# rc2014-graphics-card.net
KiCad netlist of a schematic drawn in EAGLE
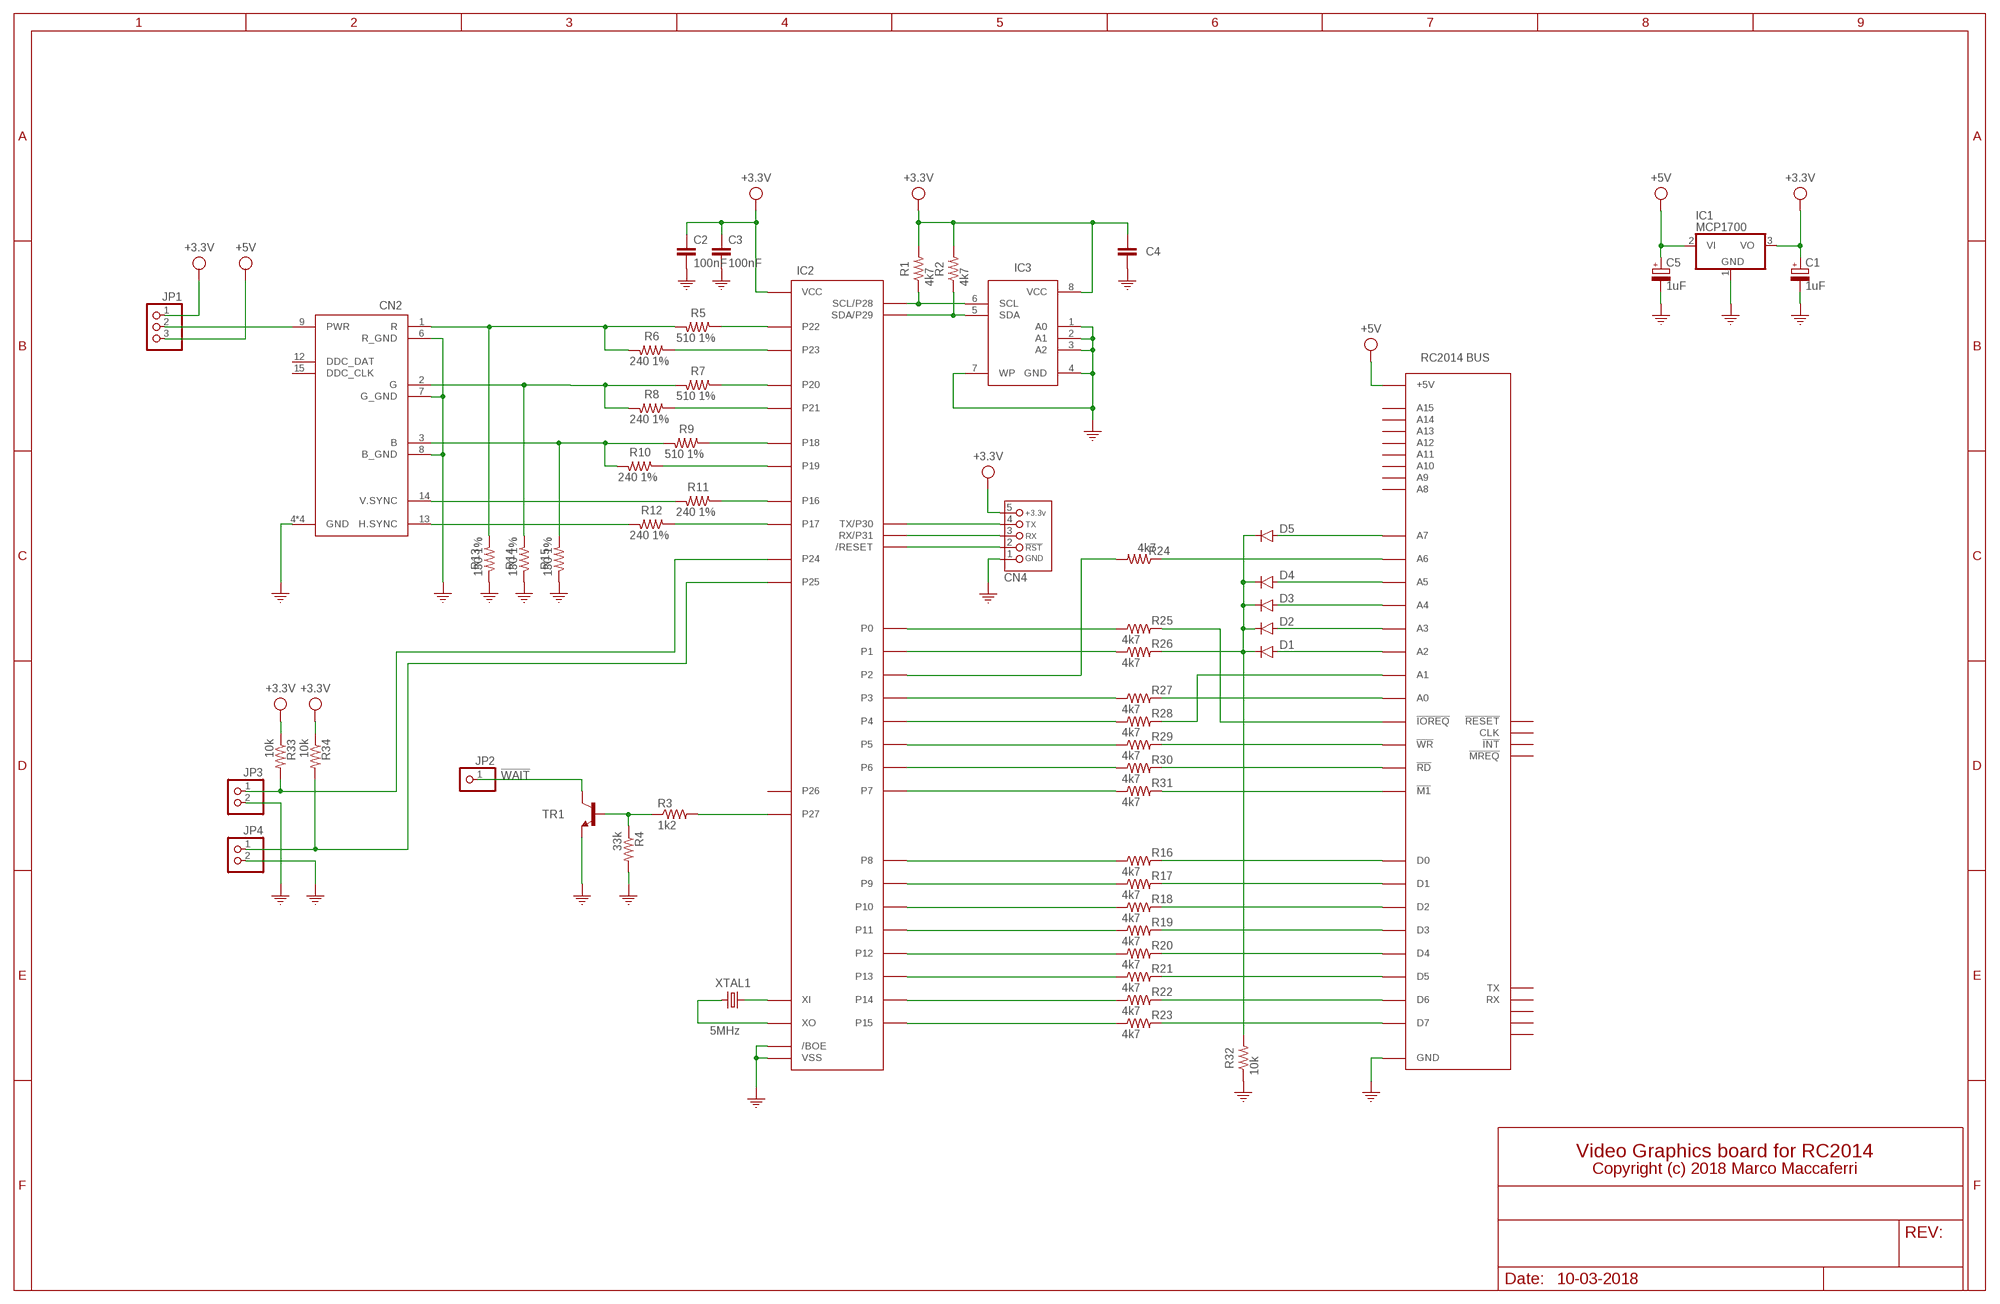
[diagram p0: schematic, sheet 1]

(export (version "E")
  (design (tool "Eeschema 10.0.6"))
  (components
    (comp (ref "C1")
      (value "1uF")
      (footprint "eagle-import:E2,5-6")
      (fields (field (name "MPN") "ESK105M050AC3AA"))
      (libsource (lib "eagle-import") (part "CP-2.5-6"))
    )
    (comp (ref "C2")
      (value "100nF")
      (footprint "eagle-import:C050-025X075")
      (fields (field (name "MPN") "R82EC3100AA70J"))
      (libsource (lib "eagle-import") (part "C"))
    )
    (comp (ref "C3")
      (value "100nF")
      (footprint "eagle-import:C050-025X075")
      (fields (field (name "MPN") "R82EC3100AA70J"))
      (libsource (lib "eagle-import") (part "C"))
    )
    (comp (ref "C4")
      (value "100nF")
      (footprint "eagle-import:C050-025X075")
      (fields (field (name "MPN") "R82EC3100AA70J"))
      (libsource (lib "eagle-import") (part "C"))
    )
    (comp (ref "C5")
      (value "1uF")
      (footprint "eagle-import:E2,5-6")
      (fields (field (name "MPN") "ESK105M050AC3AA"))
      (libsource (lib "eagle-import") (part "CP-2.5-6"))
    )
    (comp (ref "CN1")
      (value "RC2014BUS")
      (footprint "eagle-import:RC2014BUS")
      (fields (field (name "MPN") "PRPC040SBAN-M71RC"))
      (libsource (lib "eagle-import") (part "RC2014BUS"))
    )
    (comp (ref "CN2")
      (value "VGA")
      (footprint "eagle-import:VGA")
      (fields (field (name "MPN") "1734344-1"))
      (libsource (lib "eagle-import") (part "VGA"))
    )
    (comp (ref "CN4")
      (value "PROPELLER_ICSP_HEADER")
      (footprint "eagle-import:HEADER_PRG_1X05")
      (fields (field (name "MPN") "PRPC005SAAN-RC"))
      (libsource (lib "eagle-import") (part "PROPELLER_ICSP_HEADER"))
    )
    (comp (ref "D1")
      (value "1N4148DO35-7")
      (footprint "eagle-import:DO35-7")
      (libsource (lib "eagle-import") (part "1N4148DO35-7"))
    )
    (comp (ref "D2")
      (value "1N4148DO35-7")
      (footprint "eagle-import:DO35-7")
      (libsource (lib "eagle-import") (part "1N4148DO35-7"))
    )
    (comp (ref "D3")
      (value "1N4148DO35-7")
      (footprint "eagle-import:DO35-7")
      (libsource (lib "eagle-import") (part "1N4148DO35-7"))
    )
    (comp (ref "D4")
      (value "1N4148DO35-7")
      (footprint "eagle-import:DO35-7")
      (libsource (lib "eagle-import") (part "1N4148DO35-7"))
    )
    (comp (ref "D5")
      (value "1N4148DO35-7")
      (footprint "eagle-import:DO35-7")
      (libsource (lib "eagle-import") (part "1N4148DO35-7"))
    )
    (comp (ref "IC1")
      (value "MCP1700")
      (footprint "eagle-import:TO92")
      (fields (field (name "MPN") "MCP1700-3302E/TO"))
      (libsource (lib "eagle-import") (part "MCP1700"))
    )
    (comp (ref "IC2")
      (value "P8X32A-B-D40")
      (footprint "eagle-import:DIL40")
      (fields (field (name "MPN") "P8X32A-D40"))
      (libsource (lib "eagle-import") (part "P8X32A-B-D40"))
    )
    (comp (ref "IC3")
      (value "24LC512-I/P")
      (footprint "eagle-import:DIL08")
      (fields (field (name "MPN") "24LC256-I/P"))
      (libsource (lib "eagle-import") (part "24LC-I/P512"))
    )
    (comp (ref "JP1")
      (value "PINHD-1X3")
      (footprint "eagle-import:1X03")
      (libsource (lib "eagle-import") (part "PINHD-1X3"))
    )
    (comp (ref "JP2")
      (value "PINHD-1X1")
      (footprint "eagle-import:1X01")
      (libsource (lib "eagle-import") (part "PINHD-1X1"))
    )
    (comp (ref "JP3")
      (value "PINHD-1X2")
      (footprint "eagle-import:1X02")
      (libsource (lib "eagle-import") (part "PINHD-1X2"))
    )
    (comp (ref "JP4")
      (value "PINHD-1X2")
      (footprint "eagle-import:1X02")
      (libsource (lib "eagle-import") (part "PINHD-1X2"))
    )
    (comp (ref "R1")
      (value "4k7")
      (footprint "eagle-import:0207_10")
      (fields (field (name "MPN") "CFR-25JB-52-4K7"))
      (libsource (lib "eagle-import") (part "R-1/4W"))
    )
    (comp (ref "R2")
      (value "4k7")
      (footprint "eagle-import:0207_10")
      (fields (field (name "MPN") "CFR-25JB-52-4K7"))
      (libsource (lib "eagle-import") (part "R-1/4W"))
    )
    (comp (ref "R3")
      (value "1k2")
      (footprint "eagle-import:0207_10")
      (libsource (lib "eagle-import") (part "R-1/4W"))
    )
    (comp (ref "R4")
      (value "33k")
      (footprint "eagle-import:0204_7")
      (libsource (lib "eagle-import") (part "R-1/8W"))
    )
    (comp (ref "R5")
      (value "510 1%")
      (footprint "eagle-import:0207_10")
      (fields (field (name "MPN") "RNMF14FTC510R"))
      (libsource (lib "eagle-import") (part "R-1/4W"))
    )
    (comp (ref "R6")
      (value "240 1%")
      (footprint "eagle-import:0207_10")
      (fields (field (name "MPN") "RNMF14FTC240R"))
      (libsource (lib "eagle-import") (part "R-1/4W"))
    )
    (comp (ref "R7")
      (value "510 1%")
      (footprint "eagle-import:0207_10")
      (fields (field (name "MPN") "RNMF14FTC510R"))
      (libsource (lib "eagle-import") (part "R-1/4W"))
    )
    (comp (ref "R8")
      (value "240 1%")
      (footprint "eagle-import:0207_10")
      (fields (field (name "MPN") "RNMF14FTC240R"))
      (libsource (lib "eagle-import") (part "R-1/4W"))
    )
    (comp (ref "R9")
      (value "510 1%")
      (footprint "eagle-import:0207_10")
      (fields (field (name "MPN") "RNMF14FTC510R"))
      (libsource (lib "eagle-import") (part "R-1/4W"))
    )
    (comp (ref "R10")
      (value "240 1%")
      (footprint "eagle-import:0207_10")
      (fields (field (name "MPN") "RNMF14FTC240R"))
      (libsource (lib "eagle-import") (part "R-1/4W"))
    )
    (comp (ref "R11")
      (value "240 1%")
      (footprint "eagle-import:0207_10")
      (fields (field (name "MPN") "RNMF14FTC240R"))
      (libsource (lib "eagle-import") (part "R-1/4W"))
    )
    (comp (ref "R12")
      (value "240 1%")
      (footprint "eagle-import:0207_10")
      (fields (field (name "MPN") "RNMF14FTC240R"))
      (libsource (lib "eagle-import") (part "R-1/4W"))
    )
    (comp (ref "R13")
      (value "130 1%")
      (footprint "eagle-import:0207_10")
      (fields (field (name "MPN") "RNMF14FTC130R"))
      (libsource (lib "eagle-import") (part "R-1/4W"))
    )
    (comp (ref "R14")
      (value "130 1%")
      (footprint "eagle-import:0207_10")
      (fields (field (name "MPN") "RNMF14FTC130R"))
      (libsource (lib "eagle-import") (part "R-1/4W"))
    )
    (comp (ref "R15")
      (value "130 1%")
      (footprint "eagle-import:0207_10")
      (fields (field (name "MPN") "RNMF14FTC130R"))
      (libsource (lib "eagle-import") (part "R-1/4W"))
    )
    (comp (ref "R16")
      (value "4k7")
      (footprint "eagle-import:0204_7")
      (libsource (lib "eagle-import") (part "R-1/8W"))
    )
    (comp (ref "R17")
      (value "4k7")
      (footprint "eagle-import:0204_7")
      (libsource (lib "eagle-import") (part "R-1/8W"))
    )
    (comp (ref "R18")
      (value "4k7")
      (footprint "eagle-import:0204_7")
      (libsource (lib "eagle-import") (part "R-1/8W"))
    )
    (comp (ref "R19")
      (value "4k7")
      (footprint "eagle-import:0204_7")
      (libsource (lib "eagle-import") (part "R-1/8W"))
    )
    (comp (ref "R20")
      (value "4k7")
      (footprint "eagle-import:0204_7")
      (libsource (lib "eagle-import") (part "R-1/8W"))
    )
    (comp (ref "R21")
      (value "4k7")
      (footprint "eagle-import:0204_7")
      (libsource (lib "eagle-import") (part "R-1/8W"))
    )
    (comp (ref "R22")
      (value "4k7")
      (footprint "eagle-import:0204_7")
      (libsource (lib "eagle-import") (part "R-1/8W"))
    )
    (comp (ref "R23")
      (value "4k7")
      (footprint "eagle-import:0204_7")
      (libsource (lib "eagle-import") (part "R-1/8W"))
    )
    (comp (ref "R24")
      (value "4k7")
      (footprint "eagle-import:0204_7")
      (libsource (lib "eagle-import") (part "R-1/8W"))
    )
    (comp (ref "R25")
      (value "4k7")
      (footprint "eagle-import:0204_7")
      (libsource (lib "eagle-import") (part "R-1/8W"))
    )
    (comp (ref "R26")
      (value "4k7")
      (footprint "eagle-import:0204_7")
      (libsource (lib "eagle-import") (part "R-1/8W"))
    )
    (comp (ref "R27")
      (value "4k7")
      (footprint "eagle-import:0204_7")
      (libsource (lib "eagle-import") (part "R-1/8W"))
    )
    (comp (ref "R28")
      (value "4k7")
      (footprint "eagle-import:0204_7")
      (libsource (lib "eagle-import") (part "R-1/8W"))
    )
    (comp (ref "R29")
      (value "4k7")
      (footprint "eagle-import:0204_7")
      (libsource (lib "eagle-import") (part "R-1/8W"))
    )
    (comp (ref "R30")
      (value "4k7")
      (footprint "eagle-import:0204_7")
      (libsource (lib "eagle-import") (part "R-1/8W"))
    )
    (comp (ref "R31")
      (value "4k7")
      (footprint "eagle-import:0204_7")
      (libsource (lib "eagle-import") (part "R-1/8W"))
    )
    (comp (ref "R32")
      (value "10k")
      (footprint "eagle-import:0204_7")
      (libsource (lib "eagle-import") (part "R-1/8W"))
    )
    (comp (ref "R33")
      (value "10k")
      (footprint "eagle-import:0207_10")
      (libsource (lib "eagle-import") (part "R-1/4W"))
    )
    (comp (ref "R34")
      (value "10k")
      (footprint "eagle-import:0207_10")
      (libsource (lib "eagle-import") (part "R-1/4W"))
    )
    (comp (ref "TR1")
      (value "BC547A")
      (footprint "eagle-import:TO92")
      (libsource (lib "eagle-import") (part "BC547A"))
    )
    (comp (ref "XTAL1")
      (value "5MHz")
      (footprint "eagle-import:HC49_S")
      (fields (field (name "MPN") "ECS-50-20-4X"))
      (libsource (lib "eagle-import") (part "CRYSTAL-HC49/S"))
    )
  )
  (nets
    (net (code "1") (name "+3.3V") (class "Default")
      (node (ref "C1") (pin "+") (pinfunction "+_+") (pintype "passive"))
      (node (ref "C2") (pin "1") (pinfunction "1_1") (pintype "passive"))
      (node (ref "C3") (pin "1") (pinfunction "1_1") (pintype "passive"))
      (node (ref "C4") (pin "1") (pinfunction "1_1") (pintype "passive"))
      (node (ref "CN4") (pin "5") (pinfunction "5_5") (pintype "power_in"))
      (node (ref "IC1") (pin "3") (pinfunction "VO_3") (pintype "passive"))
      (node (ref "IC2") (pin "12") (pinfunction "VCC_12") (pintype "bidirectional"))
      (node (ref "IC2") (pin "32") (pinfunction "VCC_32") (pintype "bidirectional"))
      (node (ref "IC3") (pin "8") (pinfunction "VCC_8") (pintype "bidirectional"))
      (node (ref "JP1") (pin "1") (pinfunction "1_1") (pintype "passive"))
      (node (ref "R1") (pin "2") (pinfunction "2_2") (pintype "passive"))
      (node (ref "R2") (pin "2") (pinfunction "2_2") (pintype "passive"))
      (node (ref "R33") (pin "1") (pinfunction "1_1") (pintype "passive"))
      (node (ref "R34") (pin "1") (pinfunction "1_1") (pintype "passive"))
    )
    (net (code "2") (name "+5V") (class "Default")
      (node (ref "C5") (pin "+") (pinfunction "+_+") (pintype "passive"))
      (node (ref "CN1") (pin "+5V") (pinfunction "+5V_+5V") (pintype "bidirectional"))
      (node (ref "IC1") (pin "2") (pinfunction "VI_2") (pintype "input"))
      (node (ref "JP1") (pin "3") (pinfunction "3_3") (pintype "passive"))
    )
    (net (code "3") (name "/G") (class "Default")
      (node (ref "CN2") (pin "2") (pinfunction "G_2") (pintype "passive"))
      (node (ref "R14") (pin "2") (pinfunction "2_2") (pintype "passive"))
      (node (ref "R7") (pin "2") (pinfunction "2_2") (pintype "passive"))
      (node (ref "R8") (pin "2") (pinfunction "2_2") (pintype "passive"))
    )
    (net (code "4") (name "/~{WAIT}") (class "Default")
      (node (ref "JP2") (pin "1") (pinfunction "1_1") (pintype "passive"))
      (node (ref "TR1") (pin "1") (pinfunction "C_1") (pintype "passive"))
    )
    (net (code "5") (name "GND") (class "Default")
      (node (ref "C1") (pin "-") (pinfunction "-_-") (pintype "passive"))
      (node (ref "C2") (pin "2") (pinfunction "2_2") (pintype "passive"))
      (node (ref "C3") (pin "2") (pinfunction "2_2") (pintype "passive"))
      (node (ref "C4") (pin "2") (pinfunction "2_2") (pintype "passive"))
      (node (ref "C5") (pin "-") (pinfunction "-_-") (pintype "passive"))
      (node (ref "CN1") (pin "GND") (pinfunction "GND_GND") (pintype "bidirectional"))
      (node (ref "CN2") (pin "10") (pinfunction "GND_10") (pintype "passive"))
      (node (ref "CN2") (pin "11") (pinfunction "GND_11") (pintype "passive"))
      (node (ref "CN2") (pin "4") (pinfunction "GND_4") (pintype "passive"))
      (node (ref "CN2") (pin "5") (pinfunction "GND_5") (pintype "passive"))
      (node (ref "CN2") (pin "6") (pinfunction "R_GND_6") (pintype "passive"))
      (node (ref "CN2") (pin "7") (pinfunction "G_GND_7") (pintype "passive"))
      (node (ref "CN2") (pin "8") (pinfunction "B_GND_8") (pintype "passive"))
      (node (ref "CN4") (pin "1") (pinfunction "1_1") (pintype "power_in"))
      (node (ref "IC1") (pin "1") (pinfunction "GND_1") (pintype "passive"))
      (node (ref "IC2") (pin "10") (pinfunction "/BOE_10") (pintype "input"))
      (node (ref "IC2") (pin "29") (pinfunction "VSS_29") (pintype "bidirectional"))
      (node (ref "IC2") (pin "9") (pinfunction "VSS_9") (pintype "bidirectional"))
      (node (ref "IC3") (pin "1") (pinfunction "A0_1") (pintype "input"))
      (node (ref "IC3") (pin "2") (pinfunction "A1_2") (pintype "input"))
      (node (ref "IC3") (pin "3") (pinfunction "A2_3") (pintype "input"))
      (node (ref "IC3") (pin "4") (pinfunction "GND_4") (pintype "bidirectional"))
      (node (ref "IC3") (pin "7") (pinfunction "WP_7") (pintype "input"))
      (node (ref "JP3") (pin "2") (pinfunction "2_2") (pintype "passive"))
      (node (ref "JP4") (pin "2") (pinfunction "2_2") (pintype "passive"))
      (node (ref "R13") (pin "1") (pinfunction "1_1") (pintype "passive"))
      (node (ref "R14") (pin "1") (pinfunction "1_1") (pintype "passive"))
      (node (ref "R15") (pin "1") (pinfunction "1_1") (pintype "passive"))
      (node (ref "R32") (pin "1") (pinfunction "1_1") (pintype "passive"))
      (node (ref "R4") (pin "2") (pinfunction "2_2") (pintype "passive"))
      (node (ref "TR1") (pin "3") (pinfunction "E_3") (pintype "passive"))
    )
    (net (code "6") (name "Net-(CN1-PadA0)") (class "Default")
      (node (ref "CN1") (pin "A0") (pinfunction "A0_A0") (pintype "bidirectional"))
      (node (ref "R27") (pin "2") (pinfunction "2_2") (pintype "passive"))
    )
    (net (code "7") (name "Net-(CN1-PadA1)") (class "Default")
      (node (ref "CN1") (pin "A1") (pinfunction "A1_A1") (pintype "bidirectional"))
      (node (ref "R28") (pin "2") (pinfunction "2_2") (pintype "passive"))
    )
    (net (code "8") (name "Net-(CN1-PadA2)") (class "Default")
      (node (ref "CN1") (pin "A2") (pinfunction "A2_A2") (pintype "bidirectional"))
      (node (ref "D1") (pin "A") (pinfunction "A_A") (pintype "passive"))
    )
    (net (code "9") (name "Net-(CN1-PadA3)") (class "Default")
      (node (ref "CN1") (pin "A3") (pinfunction "A3_A3") (pintype "bidirectional"))
      (node (ref "D2") (pin "A") (pinfunction "A_A") (pintype "passive"))
    )
    (net (code "10") (name "Net-(CN1-PadA4)") (class "Default")
      (node (ref "CN1") (pin "A4") (pinfunction "A4_A4") (pintype "bidirectional"))
      (node (ref "D3") (pin "A") (pinfunction "A_A") (pintype "passive"))
    )
    (net (code "11") (name "Net-(CN1-PadA5)") (class "Default")
      (node (ref "CN1") (pin "A5") (pinfunction "A5_A5") (pintype "bidirectional"))
      (node (ref "D4") (pin "A") (pinfunction "A_A") (pintype "passive"))
    )
    (net (code "12") (name "Net-(CN1-PadA6)") (class "Default")
      (node (ref "CN1") (pin "A6") (pinfunction "A6_A6") (pintype "bidirectional"))
      (node (ref "R24") (pin "1") (pinfunction "1_1") (pintype "passive"))
    )
    (net (code "13") (name "Net-(CN1-PadA7)") (class "Default")
      (node (ref "CN1") (pin "A7") (pinfunction "A7_A7") (pintype "bidirectional"))
      (node (ref "D5") (pin "A") (pinfunction "A_A") (pintype "passive"))
    )
    (net (code "14") (name "Net-(CN1-PadD0)") (class "Default")
      (node (ref "CN1") (pin "D0") (pinfunction "D0_D0") (pintype "bidirectional"))
      (node (ref "R16") (pin "2") (pinfunction "2_2") (pintype "passive"))
    )
    (net (code "15") (name "Net-(CN1-PadD1)") (class "Default")
      (node (ref "CN1") (pin "D1") (pinfunction "D1_D1") (pintype "bidirectional"))
      (node (ref "R17") (pin "2") (pinfunction "2_2") (pintype "passive"))
    )
    (net (code "16") (name "Net-(CN1-PadD2)") (class "Default")
      (node (ref "CN1") (pin "D2") (pinfunction "D2_D2") (pintype "bidirectional"))
      (node (ref "R18") (pin "2") (pinfunction "2_2") (pintype "passive"))
    )
    (net (code "17") (name "Net-(CN1-PadD3)") (class "Default")
      (node (ref "CN1") (pin "D3") (pinfunction "D3_D3") (pintype "bidirectional"))
      (node (ref "R19") (pin "2") (pinfunction "2_2") (pintype "passive"))
    )
    (net (code "18") (name "Net-(CN1-PadD4)") (class "Default")
      (node (ref "CN1") (pin "D4") (pinfunction "D4_D4") (pintype "bidirectional"))
      (node (ref "R20") (pin "2") (pinfunction "2_2") (pintype "passive"))
    )
    (net (code "19") (name "Net-(CN1-PadD5)") (class "Default")
      (node (ref "CN1") (pin "D5") (pinfunction "D5_D5") (pintype "bidirectional"))
      (node (ref "R21") (pin "2") (pinfunction "2_2") (pintype "passive"))
    )
    (net (code "20") (name "Net-(CN1-PadD6)") (class "Default")
      (node (ref "CN1") (pin "D6") (pinfunction "D6_D6") (pintype "bidirectional"))
      (node (ref "R22") (pin "2") (pinfunction "2_2") (pintype "passive"))
    )
    (net (code "21") (name "Net-(CN1-PadD7)") (class "Default")
      (node (ref "CN1") (pin "D7") (pinfunction "D7_D7") (pintype "bidirectional"))
      (node (ref "R23") (pin "2") (pinfunction "2_2") (pintype "passive"))
    )
    (net (code "22") (name "Net-(CN1-~{IOREQ})") (class "Default")
      (node (ref "CN1") (pin "!IOREQ!") (pinfunction "~{IOREQ}_!IOREQ!") (pintype "bidirectional"))
      (node (ref "R25") (pin "2") (pinfunction "2_2") (pintype "passive"))
    )
    (net (code "23") (name "Net-(CN1-~{M1})") (class "Default")
      (node (ref "CN1") (pin "!M1!") (pinfunction "~{M1}_!M1!") (pintype "bidirectional"))
      (node (ref "R31") (pin "2") (pinfunction "2_2") (pintype "passive"))
    )
    (net (code "24") (name "Net-(CN1-~{RD})") (class "Default")
      (node (ref "CN1") (pin "!RD!") (pinfunction "~{RD}_!RD!") (pintype "bidirectional"))
      (node (ref "R30") (pin "2") (pinfunction "2_2") (pintype "passive"))
    )
    (net (code "25") (name "Net-(CN1-~{WR})") (class "Default")
      (node (ref "CN1") (pin "!WR!") (pinfunction "~{WR}_!WR!") (pintype "bidirectional"))
      (node (ref "R29") (pin "2") (pinfunction "2_2") (pintype "passive"))
    )
    (net (code "26") (name "Net-(CN2-B)") (class "Default")
      (node (ref "CN2") (pin "3") (pinfunction "B_3") (pintype "passive"))
      (node (ref "R10") (pin "2") (pinfunction "2_2") (pintype "passive"))
      (node (ref "R15") (pin "2") (pinfunction "2_2") (pintype "passive"))
      (node (ref "R9") (pin "2") (pinfunction "2_2") (pintype "passive"))
    )
    (net (code "27") (name "Net-(CN2-H.SYNC)") (class "Default")
      (node (ref "CN2") (pin "13") (pinfunction "H.SYNC_13") (pintype "passive"))
      (node (ref "R12") (pin "2") (pinfunction "2_2") (pintype "passive"))
    )
    (net (code "28") (name "Net-(CN2-PWR)") (class "Default")
      (node (ref "CN2") (pin "9") (pinfunction "PWR_9") (pintype "bidirectional"))
      (node (ref "JP1") (pin "2") (pinfunction "2_2") (pintype "passive"))
    )
    (net (code "29") (name "Net-(CN2-R)") (class "Default")
      (node (ref "CN2") (pin "1") (pinfunction "R_1") (pintype "passive"))
      (node (ref "R13") (pin "2") (pinfunction "2_2") (pintype "passive"))
      (node (ref "R5") (pin "2") (pinfunction "2_2") (pintype "passive"))
      (node (ref "R6") (pin "2") (pinfunction "2_2") (pintype "passive"))
    )
    (net (code "30") (name "Net-(CN2-V.SYNC)") (class "Default")
      (node (ref "CN2") (pin "14") (pinfunction "V.SYNC_14") (pintype "passive"))
      (node (ref "R11") (pin "2") (pinfunction "2_2") (pintype "passive"))
    )
    (net (code "31") (name "Net-(D1-PadC)") (class "Default")
      (node (ref "D1") (pin "C") (pinfunction "C_C") (pintype "passive"))
      (node (ref "D2") (pin "C") (pinfunction "C_C") (pintype "passive"))
      (node (ref "D3") (pin "C") (pinfunction "C_C") (pintype "passive"))
      (node (ref "D4") (pin "C") (pinfunction "C_C") (pintype "passive"))
      (node (ref "D5") (pin "C") (pinfunction "C_C") (pintype "passive"))
      (node (ref "R26") (pin "2") (pinfunction "2_2") (pintype "passive"))
      (node (ref "R32") (pin "2") (pinfunction "2_2") (pintype "passive"))
    )
    (net (code "32") (name "Net-(IC2-P0)") (class "Default")
      (node (ref "IC2") (pin "1") (pinfunction "P0_1") (pintype "bidirectional"))
      (node (ref "R25") (pin "1") (pinfunction "1_1") (pintype "passive"))
    )
    (net (code "33") (name "Net-(IC2-P1)") (class "Default")
      (node (ref "IC2") (pin "2") (pinfunction "P1_2") (pintype "bidirectional"))
      (node (ref "R26") (pin "1") (pinfunction "1_1") (pintype "passive"))
    )
    (net (code "34") (name "Net-(IC2-P2)") (class "Default")
      (node (ref "IC2") (pin "3") (pinfunction "P2_3") (pintype "bidirectional"))
      (node (ref "R24") (pin "2") (pinfunction "2_2") (pintype "passive"))
    )
    (net (code "35") (name "Net-(IC2-P3)") (class "Default")
      (node (ref "IC2") (pin "4") (pinfunction "P3_4") (pintype "bidirectional"))
      (node (ref "R27") (pin "1") (pinfunction "1_1") (pintype "passive"))
    )
    (net (code "36") (name "Net-(IC2-P4)") (class "Default")
      (node (ref "IC2") (pin "5") (pinfunction "P4_5") (pintype "bidirectional"))
      (node (ref "R28") (pin "1") (pinfunction "1_1") (pintype "passive"))
    )
    (net (code "37") (name "Net-(IC2-P5)") (class "Default")
      (node (ref "IC2") (pin "6") (pinfunction "P5_6") (pintype "bidirectional"))
      (node (ref "R29") (pin "1") (pinfunction "1_1") (pintype "passive"))
    )
    (net (code "38") (name "Net-(IC2-P6)") (class "Default")
      (node (ref "IC2") (pin "7") (pinfunction "P6_7") (pintype "bidirectional"))
      (node (ref "R30") (pin "1") (pinfunction "1_1") (pintype "passive"))
    )
    (net (code "39") (name "Net-(IC2-P7)") (class "Default")
      (node (ref "IC2") (pin "8") (pinfunction "P7_8") (pintype "bidirectional"))
      (node (ref "R31") (pin "1") (pinfunction "1_1") (pintype "passive"))
    )
    (net (code "40") (name "Net-(IC2-P8)") (class "Default")
      (node (ref "IC2") (pin "13") (pinfunction "P8_13") (pintype "bidirectional"))
      (node (ref "R16") (pin "1") (pinfunction "1_1") (pintype "passive"))
    )
    (net (code "41") (name "Net-(IC2-P9)") (class "Default")
      (node (ref "IC2") (pin "14") (pinfunction "P9_14") (pintype "bidirectional"))
      (node (ref "R17") (pin "1") (pinfunction "1_1") (pintype "passive"))
    )
    (net (code "42") (name "Net-(IC2-P10)") (class "Default")
      (node (ref "IC2") (pin "15") (pinfunction "P10_15") (pintype "bidirectional"))
      (node (ref "R18") (pin "1") (pinfunction "1_1") (pintype "passive"))
    )
    (net (code "43") (name "Net-(IC2-P11)") (class "Default")
      (node (ref "IC2") (pin "16") (pinfunction "P11_16") (pintype "bidirectional"))
      (node (ref "R19") (pin "1") (pinfunction "1_1") (pintype "passive"))
    )
    (net (code "44") (name "Net-(IC2-P12)") (class "Default")
      (node (ref "IC2") (pin "17") (pinfunction "P12_17") (pintype "bidirectional"))
      (node (ref "R20") (pin "1") (pinfunction "1_1") (pintype "passive"))
    )
    (net (code "45") (name "Net-(IC2-P13)") (class "Default")
      (node (ref "IC2") (pin "18") (pinfunction "P13_18") (pintype "bidirectional"))
      (node (ref "R21") (pin "1") (pinfunction "1_1") (pintype "passive"))
    )
    (net (code "46") (name "Net-(IC2-P14)") (class "Default")
      (node (ref "IC2") (pin "19") (pinfunction "P14_19") (pintype "bidirectional"))
      (node (ref "R22") (pin "1") (pinfunction "1_1") (pintype "passive"))
    )
    (net (code "47") (name "Net-(IC2-P15)") (class "Default")
      (node (ref "IC2") (pin "20") (pinfunction "P15_20") (pintype "bidirectional"))
      (node (ref "R23") (pin "1") (pinfunction "1_1") (pintype "passive"))
    )
    (net (code "48") (name "Net-(IC2-P16)") (class "Default")
      (node (ref "IC2") (pin "21") (pinfunction "P16_21") (pintype "bidirectional"))
      (node (ref "R11") (pin "1") (pinfunction "1_1") (pintype "passive"))
    )
    (net (code "49") (name "Net-(IC2-P17)") (class "Default")
      (node (ref "IC2") (pin "22") (pinfunction "P17_22") (pintype "bidirectional"))
      (node (ref "R12") (pin "1") (pinfunction "1_1") (pintype "passive"))
    )
    (net (code "50") (name "Net-(IC2-P18)") (class "Default")
      (node (ref "IC2") (pin "23") (pinfunction "P18_23") (pintype "bidirectional"))
      (node (ref "R9") (pin "1") (pinfunction "1_1") (pintype "passive"))
    )
    (net (code "51") (name "Net-(IC2-P19)") (class "Default")
      (node (ref "IC2") (pin "24") (pinfunction "P19_24") (pintype "bidirectional"))
      (node (ref "R10") (pin "1") (pinfunction "1_1") (pintype "passive"))
    )
    (net (code "52") (name "Net-(IC2-P20)") (class "Default")
      (node (ref "IC2") (pin "25") (pinfunction "P20_25") (pintype "bidirectional"))
      (node (ref "R7") (pin "1") (pinfunction "1_1") (pintype "passive"))
    )
    (net (code "53") (name "Net-(IC2-P21)") (class "Default")
      (node (ref "IC2") (pin "26") (pinfunction "P21_26") (pintype "bidirectional"))
      (node (ref "R8") (pin "1") (pinfunction "1_1") (pintype "passive"))
    )
    (net (code "54") (name "Net-(IC2-P22)") (class "Default")
      (node (ref "IC2") (pin "27") (pinfunction "P22_27") (pintype "bidirectional"))
      (node (ref "R5") (pin "1") (pinfunction "1_1") (pintype "passive"))
    )
    (net (code "55") (name "Net-(IC2-P23)") (class "Default")
      (node (ref "IC2") (pin "28") (pinfunction "P23_28") (pintype "bidirectional"))
      (node (ref "R6") (pin "1") (pinfunction "1_1") (pintype "passive"))
    )
    (net (code "56") (name "Net-(IC2-P24)") (class "Default")
      (node (ref "IC2") (pin "33") (pinfunction "P24_33") (pintype "bidirectional"))
      (node (ref "JP3") (pin "1") (pinfunction "1_1") (pintype "passive"))
      (node (ref "R33") (pin "2") (pinfunction "2_2") (pintype "passive"))
    )
    (net (code "57") (name "Net-(IC2-P25)") (class "Default")
      (node (ref "IC2") (pin "34") (pinfunction "P25_34") (pintype "bidirectional"))
      (node (ref "JP4") (pin "1") (pinfunction "1_1") (pintype "passive"))
      (node (ref "R34") (pin "2") (pinfunction "2_2") (pintype "passive"))
    )
    (net (code "58") (name "Net-(IC2-P27)") (class "Default")
      (node (ref "IC2") (pin "36") (pinfunction "P27_36") (pintype "bidirectional"))
      (node (ref "R3") (pin "2") (pinfunction "2_2") (pintype "passive"))
    )
    (net (code "59") (name "Net-(IC2-RX{slash}P31)") (class "Default")
      (node (ref "CN4") (pin "3") (pinfunction "3_3") (pintype "input"))
      (node (ref "IC2") (pin "40") (pinfunction "RX/P31_40") (pintype "bidirectional"))
    )
    (net (code "60") (name "Net-(IC2-SCL{slash}P28)") (class "Default")
      (node (ref "IC2") (pin "37") (pinfunction "SCL/P28_37") (pintype "bidirectional"))
      (node (ref "IC3") (pin "6") (pinfunction "SCL_6") (pintype "bidirectional"))
      (node (ref "R1") (pin "1") (pinfunction "1_1") (pintype "passive"))
    )
    (net (code "61") (name "Net-(IC2-SDA{slash}P29)") (class "Default")
      (node (ref "IC2") (pin "38") (pinfunction "SDA/P29_38") (pintype "bidirectional"))
      (node (ref "IC3") (pin "5") (pinfunction "SDA_5") (pintype "bidirectional"))
      (node (ref "R2") (pin "1") (pinfunction "1_1") (pintype "passive"))
    )
    (net (code "62") (name "Net-(IC2-TX{slash}P30)") (class "Default")
      (node (ref "CN4") (pin "4") (pinfunction "4_4") (pintype "output"))
      (node (ref "IC2") (pin "39") (pinfunction "TX/P30_39") (pintype "bidirectional"))
    )
    (net (code "63") (name "Net-(IC2-XI)") (class "Default")
      (node (ref "IC2") (pin "30") (pinfunction "XI_30") (pintype "open_collector"))
      (node (ref "XTAL1") (pin "1") (pinfunction "1_1") (pintype "passive"))
    )
    (net (code "64") (name "Net-(IC2-XO)") (class "Default")
      (node (ref "IC2") (pin "31") (pinfunction "XO_31") (pintype "open_collector"))
      (node (ref "XTAL1") (pin "2") (pinfunction "2_2") (pintype "passive"))
    )
    (net (code "65") (name "Net-(IC2-{slash}RESET)") (class "Default")
      (node (ref "CN4") (pin "2") (pinfunction "2_2") (pintype "input"))
      (node (ref "IC2") (pin "11") (pinfunction "/RESET_11") (pintype "bidirectional"))
    )
    (net (code "66") (name "Net-(TR1-B)") (class "Default")
      (node (ref "R3") (pin "1") (pinfunction "1_1") (pintype "passive"))
      (node (ref "R4") (pin "1") (pinfunction "1_1") (pintype "passive"))
      (node (ref "TR1") (pin "2") (pinfunction "B_2") (pintype "passive"))
    )
    (net (code "67") (name "unconnected-(CN1-PadA8)") (class "Default")
      (node (ref "CN1") (pin "A8") (pinfunction "A8_A8") (pintype "bidirectional"))
    )
    (net (code "68") (name "unconnected-(CN1-PadA9)") (class "Default")
      (node (ref "CN1") (pin "A9") (pinfunction "A9_A9") (pintype "bidirectional"))
    )
    (net (code "69") (name "unconnected-(CN1-PadA10)") (class "Default")
      (node (ref "CN1") (pin "A10") (pinfunction "A10_A10") (pintype "bidirectional"))
    )
    (net (code "70") (name "unconnected-(CN1-PadA11)") (class "Default")
      (node (ref "CN1") (pin "A11") (pinfunction "A11_A11") (pintype "bidirectional"))
    )
    (net (code "71") (name "unconnected-(CN1-PadA12)") (class "Default")
      (node (ref "CN1") (pin "A12") (pinfunction "A12_A12") (pintype "bidirectional"))
    )
    (net (code "72") (name "unconnected-(CN1-PadA13)") (class "Default")
      (node (ref "CN1") (pin "A13") (pinfunction "A13_A13") (pintype "bidirectional"))
    )
    (net (code "73") (name "unconnected-(CN1-PadA14)") (class "Default")
      (node (ref "CN1") (pin "A14") (pinfunction "A14_A14") (pintype "bidirectional"))
    )
    (net (code "74") (name "unconnected-(CN1-PadA15)") (class "Default")
      (node (ref "CN1") (pin "A15") (pinfunction "A15_A15") (pintype "bidirectional"))
    )
    (net (code "75") (name "unconnected-(CN1-PadCLK)") (class "Default")
      (node (ref "CN1") (pin "CLK") (pinfunction "CLK_CLK") (pintype "bidirectional"))
    )
    (net (code "76") (name "unconnected-(CN1-PadRX)") (class "Default")
      (node (ref "CN1") (pin "RX") (pinfunction "RX_RX") (pintype "bidirectional"))
    )
    (net (code "77") (name "unconnected-(CN1-PadSPARE1)") (class "Default")
      (node (ref "CN1") (pin "SPARE1") (pinfunction "SPARE1_SPARE1") (pintype "bidirectional"))
    )
    (net (code "78") (name "unconnected-(CN1-PadSPARE2)") (class "Default")
      (node (ref "CN1") (pin "SPARE2") (pinfunction "SPARE2_SPARE2") (pintype "bidirectional"))
    )
    (net (code "79") (name "unconnected-(CN1-PadSPARE3)") (class "Default")
      (node (ref "CN1") (pin "SPARE3") (pinfunction "SPARE3_SPARE3") (pintype "bidirectional"))
    )
    (net (code "80") (name "unconnected-(CN1-PadTX)") (class "Default")
      (node (ref "CN1") (pin "TX") (pinfunction "TX_TX") (pintype "bidirectional"))
    )
    (net (code "81") (name "unconnected-(CN1-~{INT}-Pad!INT!)") (class "Default")
      (node (ref "CN1") (pin "!INT!") (pinfunction "~{INT}_!INT!") (pintype "bidirectional"))
    )
    (net (code "82") (name "unconnected-(CN1-~{MREQ}-Pad!MREQ!)") (class "Default")
      (node (ref "CN1") (pin "!MREQ!") (pinfunction "~{MREQ}_!MREQ!") (pintype "bidirectional"))
    )
    (net (code "83") (name "unconnected-(CN1-~{RESET}-Pad!RESET!)") (class "Default")
      (node (ref "CN1") (pin "!RESET!") (pinfunction "~{RESET}_!RESET!") (pintype "bidirectional"))
    )
    (net (code "84") (name "unconnected-(CN2-DDC_CLK-Pad15)") (class "Default")
      (node (ref "CN2") (pin "15") (pinfunction "DDC_CLK_15") (pintype "passive"))
    )
    (net (code "85") (name "unconnected-(CN2-DDC_DAT-Pad12)") (class "Default")
      (node (ref "CN2") (pin "12") (pinfunction "DDC_DAT_12") (pintype "passive"))
    )
    (net (code "86") (name "unconnected-(IC2-P26-Pad35)") (class "Default")
      (node (ref "IC2") (pin "35") (pinfunction "P26_35") (pintype "bidirectional"))
    )
  )
)
